# ReferenceVoltage.net
KiCad netlist of a schematic drawn in Altium Designer
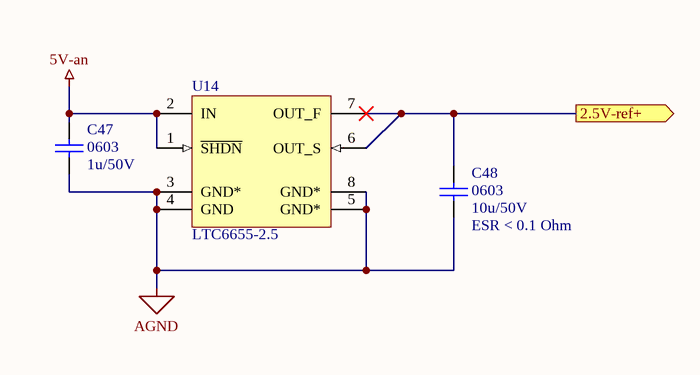
[diagram p0: ReferenceVoltage.SchDoc]

(export (version "E")
  (design (tool "Eeschema 10.0.6"))
  (components
    (comp (ref "C47")
      (value "0603")
      (footprint "SMD_Capacitor_0603")
      (description "Capacitor")
      (fields (field (name "ALTIUM_VALUE") "1u/50V") (field (name "PUBLISHER") "Altium Limited"))
      (libsource (lib "Miscellaneous Devices") (part "Cap"))
    )
    (comp (ref "C48")
      (value "ESR < 0.1 Ohm")
      (footprint "SMD_Capacitor_0603")
      (description "Capacitor")
      (fields (field (name "ALTIUM_VALUE") "10u/50V") (field (name "PUBLISHER") "Altium Limited"))
      (libsource (lib "Miscellaneous Devices") (part "Cap"))
    )
    (comp (ref "U14")
      (value "LTC6655-2.5")
      (footprint "MSOP-8")
      (description "0.25ppm Noise, Low Drift  Precision References")
      (libsource (lib "microcircuits_linear-voltage-regulator") (part "LTC6655-2.5"))
    )
  )
  (nets
    (net (code "1") (name "/2.5V-ref+") (class "Default")
      (node (ref "C48") (pin "2") (pinfunction "2_2") (pintype "passive"))
      (node (ref "U14") (pin "6") (pinfunction "OUT_S_6") (pintype "input"))
      (node (ref "U14") (pin "7") (pinfunction "OUT_F_7") (pintype "power_in"))
    )
    (net (code "2") (name "5V-an") (class "Default")
      (node (ref "C47") (pin "2") (pinfunction "2_2") (pintype "passive"))
      (node (ref "U14") (pin "1") (pinfunction "~{SHDN}_1") (pintype "input"))
      (node (ref "U14") (pin "2") (pinfunction "IN_2") (pintype "power_in"))
    )
    (net (code "3") (name "AGND") (class "Default")
      (node (ref "C47") (pin "1") (pinfunction "1_1") (pintype "passive"))
      (node (ref "C48") (pin "1") (pinfunction "1_1") (pintype "passive"))
      (node (ref "U14") (pin "3") (pinfunction "GND*_3") (pintype "power_in"))
      (node (ref "U14") (pin "4") (pinfunction "GND_4") (pintype "power_in"))
      (node (ref "U14") (pin "5") (pinfunction "GND*_5") (pintype "power_in"))
      (node (ref "U14") (pin "8") (pinfunction "GND*_8") (pintype "power_in"))
    )
  )
)
